# OmneticsAdaptorDoubleHeadstage.net
KiCad netlist of a schematic drawn in EAGLE
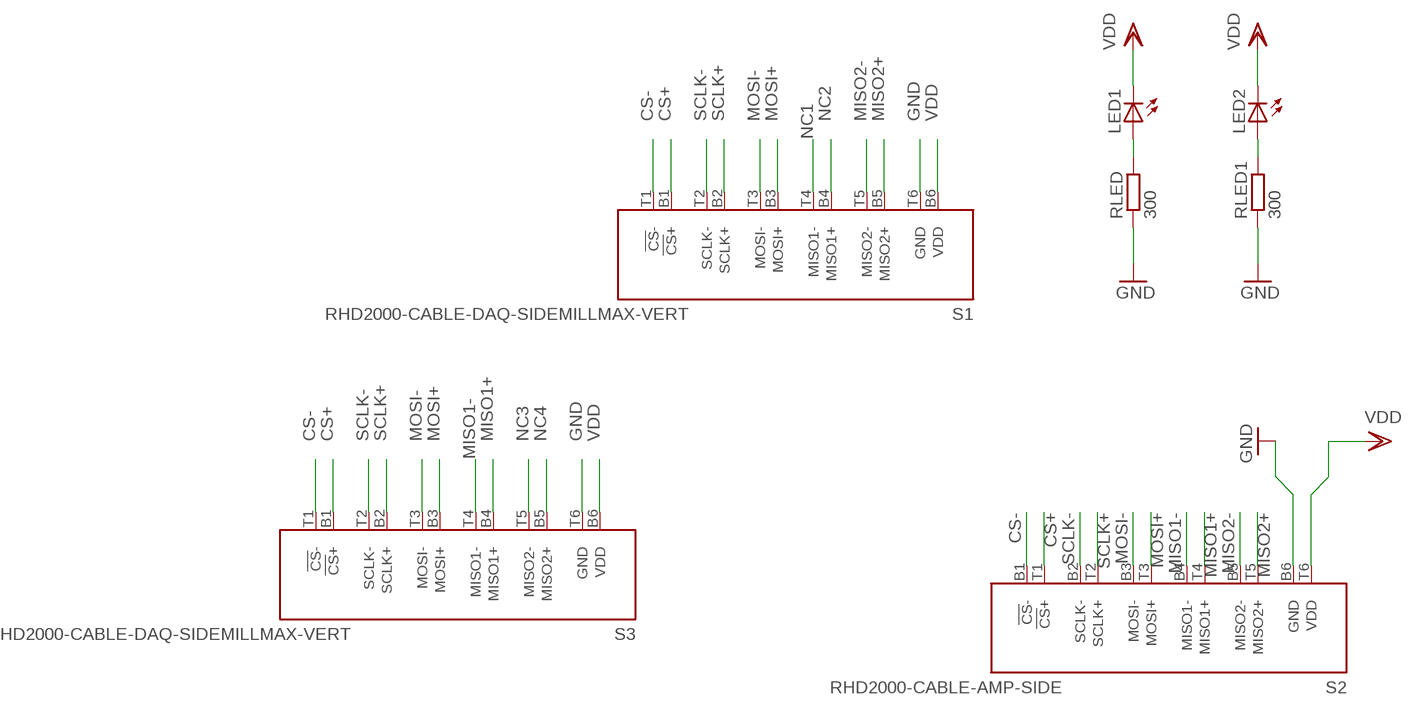
[diagram p0: schematic, sheet 1]

(export (version "E")
  (design (tool "Eeschema 10.0.6"))
  (components
    (comp (ref "LED1")
      (value "LEDCHIPLED_0805")
      (footprint "eagle-import:CHIPLED_0805")
      (libsource (lib "eagle-import") (part "LEDCHIPLED_0805"))
    )
    (comp (ref "LED2")
      (value "LEDCHIPLED_0805")
      (footprint "eagle-import:CHIPLED_0805")
      (libsource (lib "eagle-import") (part "LEDCHIPLED_0805"))
    )
    (comp (ref "RLED")
      (value "300")
      (footprint "eagle-import:R0402")
      (libsource (lib "eagle-import") (part "R-EU_R0402"))
    )
    (comp (ref "RLED1")
      (value "300")
      (footprint "eagle-import:R0402")
      (libsource (lib "eagle-import") (part "R-EU_R0402"))
    )
    (comp (ref "S1")
      (value "RHD2000-CABLE-DAQ-SIDEMILLMAX-VERT")
      (footprint "eagle-import:MILLMAX-12PIN-VERT")
      (libsource (lib "eagle-import") (part "RHD2000-CABLE-DAQ-SIDEMILLMAX-VERT"))
    )
    (comp (ref "S2")
      (value "RHD2000-CABLE-AMP-SIDE")
      (footprint "eagle-import:OMNETICS_PZN-12-AA")
      (libsource (lib "eagle-import") (part "RHD2000-CABLE-AMP-SIDE"))
    )
    (comp (ref "S3")
      (value "RHD2000-CABLE-DAQ-SIDEMILLMAX-VERT")
      (footprint "eagle-import:MILLMAX-12PIN-VERT")
      (libsource (lib "eagle-import") (part "RHD2000-CABLE-DAQ-SIDEMILLMAX-VERT"))
    )
  )
  (nets
    (net (code "1") (name "/CS+") (class "Default")
      (node (ref "S1") (pin "B1") (pinfunction "~{CS}+_B1") (pintype "bidirectional"))
      (node (ref "S2") (pin "T1") (pinfunction "~{CS}+_T1") (pintype "bidirectional"))
      (node (ref "S3") (pin "B1") (pinfunction "~{CS}+_B1") (pintype "bidirectional"))
    )
    (net (code "2") (name "/CS-") (class "Default")
      (node (ref "S1") (pin "T1") (pinfunction "~{CS}-_T1") (pintype "bidirectional"))
      (node (ref "S2") (pin "B1") (pinfunction "~{CS}-_B1") (pintype "bidirectional"))
      (node (ref "S3") (pin "T1") (pinfunction "~{CS}-_T1") (pintype "bidirectional"))
    )
    (net (code "3") (name "/MISO1+") (class "Default")
      (node (ref "S2") (pin "T4") (pinfunction "MISO1+_T4") (pintype "bidirectional"))
      (node (ref "S3") (pin "B4") (pinfunction "MISO1+_B4") (pintype "bidirectional"))
    )
    (net (code "4") (name "/MISO1-") (class "Default")
      (node (ref "S2") (pin "B4") (pinfunction "MISO1-_B4") (pintype "bidirectional"))
      (node (ref "S3") (pin "T4") (pinfunction "MISO1-_T4") (pintype "bidirectional"))
    )
    (net (code "5") (name "/MISO2+") (class "Default")
      (node (ref "S1") (pin "B5") (pinfunction "MISO2+_B5") (pintype "bidirectional"))
      (node (ref "S2") (pin "T5") (pinfunction "MISO2+_T5") (pintype "bidirectional"))
    )
    (net (code "6") (name "/MISO2-") (class "Default")
      (node (ref "S1") (pin "T5") (pinfunction "MISO2-_T5") (pintype "bidirectional"))
      (node (ref "S2") (pin "B5") (pinfunction "MISO2-_B5") (pintype "bidirectional"))
    )
    (net (code "7") (name "/MOSI+") (class "Default")
      (node (ref "S1") (pin "B3") (pinfunction "MOSI+_B3") (pintype "bidirectional"))
      (node (ref "S2") (pin "T3") (pinfunction "MOSI+_T3") (pintype "bidirectional"))
      (node (ref "S3") (pin "B3") (pinfunction "MOSI+_B3") (pintype "bidirectional"))
    )
    (net (code "8") (name "/MOSI-") (class "Default")
      (node (ref "S1") (pin "T3") (pinfunction "MOSI-_T3") (pintype "bidirectional"))
      (node (ref "S2") (pin "B3") (pinfunction "MOSI-_B3") (pintype "bidirectional"))
      (node (ref "S3") (pin "T3") (pinfunction "MOSI-_T3") (pintype "bidirectional"))
    )
    (net (code "9") (name "/NC1") (class "Default")
      (node (ref "S1") (pin "T4") (pinfunction "MISO1-_T4") (pintype "bidirectional"))
    )
    (net (code "10") (name "/NC2") (class "Default")
      (node (ref "S1") (pin "B4") (pinfunction "MISO1+_B4") (pintype "bidirectional"))
    )
    (net (code "11") (name "/NC3") (class "Default")
      (node (ref "S3") (pin "T5") (pinfunction "MISO2-_T5") (pintype "bidirectional"))
    )
    (net (code "12") (name "/NC4") (class "Default")
      (node (ref "S3") (pin "B5") (pinfunction "MISO2+_B5") (pintype "bidirectional"))
    )
    (net (code "13") (name "/SCLK+") (class "Default")
      (node (ref "S1") (pin "B2") (pinfunction "SCLK+_B2") (pintype "bidirectional"))
      (node (ref "S2") (pin "T2") (pinfunction "SCLK+_T2") (pintype "bidirectional"))
      (node (ref "S3") (pin "B2") (pinfunction "SCLK+_B2") (pintype "bidirectional"))
    )
    (net (code "14") (name "/SCLK-") (class "Default")
      (node (ref "S1") (pin "T2") (pinfunction "SCLK-_T2") (pintype "bidirectional"))
      (node (ref "S2") (pin "B2") (pinfunction "SCLK-_B2") (pintype "bidirectional"))
      (node (ref "S3") (pin "T2") (pinfunction "SCLK-_T2") (pintype "bidirectional"))
    )
    (net (code "15") (name "GND") (class "Default")
      (node (ref "RLED") (pin "1") (pinfunction "1_1") (pintype "passive"))
      (node (ref "RLED1") (pin "1") (pinfunction "1_1") (pintype "passive"))
      (node (ref "S1") (pin "T6") (pinfunction "GND_T6") (pintype "power_in"))
      (node (ref "S2") (pin "B6") (pinfunction "GND_B6") (pintype "power_in"))
      (node (ref "S3") (pin "T6") (pinfunction "GND_T6") (pintype "power_in"))
    )
    (net (code "16") (name "Net-(LED1-PadA)") (class "Default")
      (node (ref "LED1") (pin "A") (pinfunction "A_A") (pintype "passive"))
      (node (ref "RLED") (pin "2") (pinfunction "2_2") (pintype "passive"))
    )
    (net (code "17") (name "Net-(LED2-PadA)") (class "Default")
      (node (ref "LED2") (pin "A") (pinfunction "A_A") (pintype "passive"))
      (node (ref "RLED1") (pin "2") (pinfunction "2_2") (pintype "passive"))
    )
    (net (code "18") (name "VDD") (class "Default")
      (node (ref "LED1") (pin "C") (pinfunction "C_C") (pintype "passive"))
      (node (ref "LED2") (pin "C") (pinfunction "C_C") (pintype "passive"))
      (node (ref "S1") (pin "B6") (pinfunction "VDD_B6") (pintype "bidirectional"))
      (node (ref "S2") (pin "T6") (pinfunction "VDD_T6") (pintype "bidirectional"))
      (node (ref "S3") (pin "B6") (pinfunction "VDD_B6") (pintype "bidirectional"))
    )
  )
)
